# PROC099B_LC_Filtering_Reference.net
KiCad netlist of a schematic drawn in Altium Designer
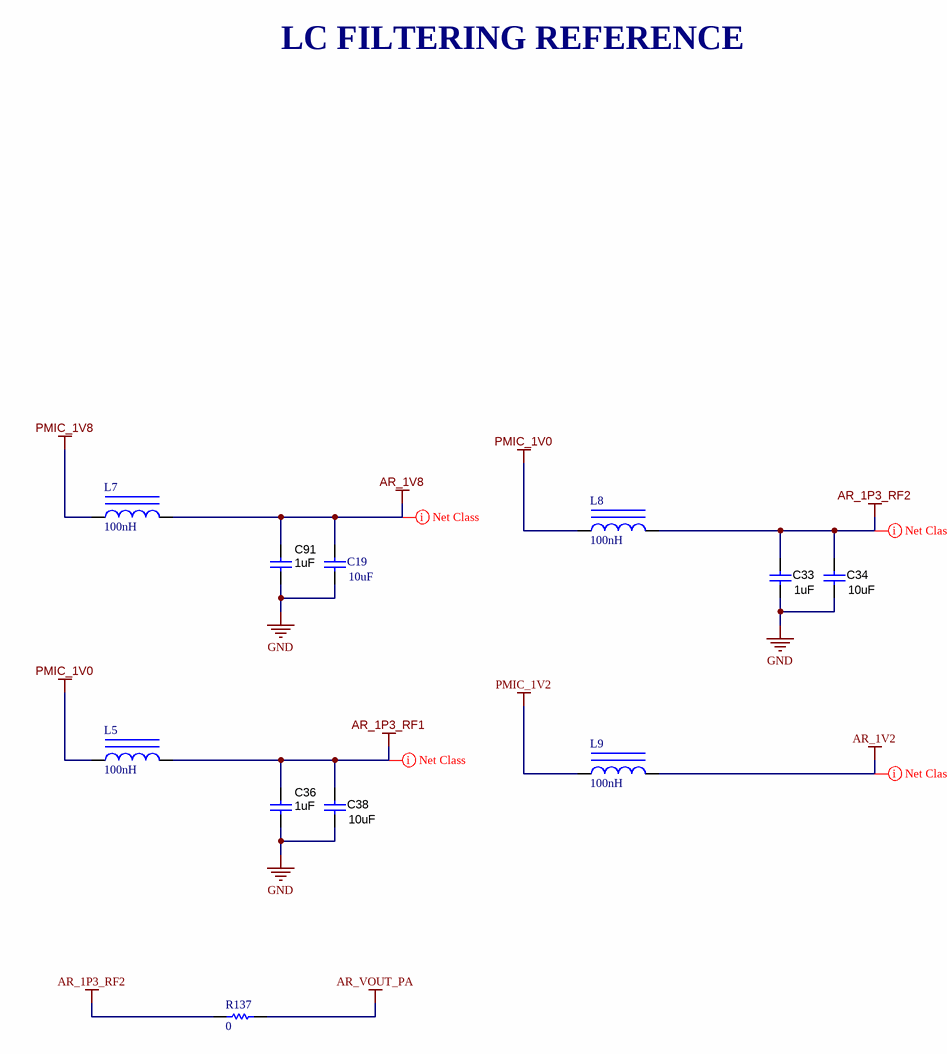
[diagram p0: PROC099B_LC_Filtering_Reference.SchDoc]

(export (version "E")
  (design (tool "Eeschema 10.0.6"))
  (components
    (comp (ref "C19")
      (value "GCM21BR71A106KE22L")
      (footprint "0805_HV")
      (description "CAP, CERM, 10 uF, 10 V, +/- 10%, X7R, 0805")
      (fields
        (field (name "MANUFACTURER") "MuRata")
        (field (name "VALUEDISPLAYED") "10uF")
        (field (name "PUBLISHER") "Texas Instruments")
      )
      (libsource (lib "Altium Vault - TI") (part "Capacitor"))
    )
    (comp (ref "C33")
      (value "GCM188R71C105KA64D")
      (footprint "0603")
      (description "CAP, CERM, 1 uF, 16 V, +/- 10%, X7R, AEC-Q200 Grade 1, 0603")
      (fields
        (field (name "MANUFACTURER") "MuRata")
        (field (name "VALUEDISPLAYED") "1uF")
        (field (name "PUBLISHER") "Texas Instruments")
      )
      (libsource (lib "Altium Vault - TI") (part "Capacitor"))
    )
    (comp (ref "C34")
      (value "GCM21BR71A106KE22L")
      (footprint "0805_HV")
      (description "CAP, CERM, 10 uF, 10 V, +/- 10%, X7R, 0805")
      (fields
        (field (name "MANUFACTURER") "MuRata")
        (field (name "VALUEDISPLAYED") "10uF")
        (field (name "PUBLISHER") "Texas Instruments")
      )
      (libsource (lib "Altium Vault - TI") (part "CMP-0008017-2"))
    )
    (comp (ref "C36")
      (value "GCM188R71C105KA64D")
      (footprint "0603")
      (description "CAP, CERM, 1 uF, 16 V, +/- 10%, X7R, AEC-Q200 Grade 1, 0603")
      (fields
        (field (name "MANUFACTURER") "MuRata")
        (field (name "VALUEDISPLAYED") "1uF")
        (field (name "PUBLISHER") "Texas Instruments")
      )
      (libsource (lib "Altium Vault - TI") (part "Capacitor"))
    )
    (comp (ref "C38")
      (value "GCM21BR71A106KE22L")
      (footprint "0805_HV")
      (description "CAP, CERM, 10 uF, 10 V, +/- 10%, X7R, 0805")
      (fields
        (field (name "MANUFACTURER") "MuRata")
        (field (name "VALUEDISPLAYED") "10uF")
        (field (name "PUBLISHER") "Texas Instruments")
      )
      (libsource (lib "Altium Vault - TI") (part "CMP-0008017-2"))
    )
    (comp (ref "C91")
      (value "GCM188R71C105KA64D")
      (footprint "0603")
      (description "CAP, CERM, 1 uF, 16 V, +/- 10%, X7R, AEC-Q200 Grade 1, 0603")
      (fields
        (field (name "MANUFACTURER") "MuRata")
        (field (name "VALUEDISPLAYED") "1uF")
        (field (name "PUBLISHER") "Texas Instruments")
      )
      (libsource (lib "Altium Vault - TI") (part "Capacitor"))
    )
    (comp (ref "L5")
      (value "NLCV32T-R10M-EFRD")
      (footprint "NLCV32")
      (description "Inductor, Wirewound, Ferrite, 100 nH, 2.85 A, 0.024 ohm, AEC-Q200 Grade 1, SMD")
      (fields (field (name "MANUFACTURER") "TDK") (field (name "VALUEDISPLAYED") "100nH"))
      (libsource (lib "Altium Vault - TI") (part "Inductor_Iron"))
    )
    (comp (ref "L7")
      (value "NLCV32T-R10M-EFRD")
      (footprint "NLCV32")
      (description "Inductor, Wirewound, Ferrite, 100 nH, 2.85 A, 0.024 ohm, AEC-Q200 Grade 1, SMD")
      (fields (field (name "MANUFACTURER") "TDK") (field (name "VALUEDISPLAYED") "100nH"))
      (libsource (lib "Altium Vault - TI") (part "Inductor_Iron"))
    )
    (comp (ref "L8")
      (value "NLCV32T-R10M-EFRD")
      (footprint "NLCV32")
      (description "Inductor, Wirewound, Ferrite, 100 nH, 2.85 A, 0.024 ohm, AEC-Q200 Grade 1, SMD")
      (fields (field (name "MANUFACTURER") "TDK") (field (name "VALUEDISPLAYED") "100nH"))
      (libsource (lib "Altium Vault - TI") (part "Inductor_Iron"))
    )
    (comp (ref "L9")
      (value "NLCV32T-R10M-EFRD")
      (footprint "NLCV32")
      (description "Inductor, Wirewound, Ferrite, 100 nH, 2.85 A, 0.024 ohm, AEC-Q200 Grade 1, SMD")
      (fields (field (name "MANUFACTURER") "TDK") (field (name "VALUEDISPLAYED") "100nH"))
      (libsource (lib "Altium Vault - TI") (part "Inductor_Iron"))
    )
    (comp (ref "R137")
      (value "MCT06030Z0000ZP500")
      (footprint "0603")
      (description "RES, 0, 5%, 0.125 W, 0603")
      (fields
        (field (name "MANUFACTURER") "Vishay/Beyschlag")
        (field (name "VALUEDISPLAYED") "0")
        (field (name "PUBLISHER") "Texas Instruments")
      )
      (libsource (lib "Altium Vault - TI") (part "CMP-0025884-3"))
    )
  )
  (nets
    (net (code "1") (name "AR_1P3_RF1") (class "Default")
      (node (ref "C36") (pin "2") (pinfunction "2_2") (pintype "passive"))
      (node (ref "C38") (pin "2") (pinfunction "2_2") (pintype "passive"))
      (node (ref "L5") (pin "2") (pinfunction "2_2") (pintype "passive"))
    )
    (net (code "2") (name "AR_1P3_RF2") (class "Default")
      (node (ref "C33") (pin "2") (pinfunction "2_2") (pintype "passive"))
      (node (ref "C34") (pin "2") (pinfunction "2_2") (pintype "passive"))
      (node (ref "L8") (pin "2") (pinfunction "2_2") (pintype "passive"))
      (node (ref "R137") (pin "1") (pinfunction "1_1") (pintype "passive"))
    )
    (net (code "3") (name "AR_1V2") (class "Default")
      (node (ref "L9") (pin "2") (pinfunction "2_2") (pintype "passive"))
    )
    (net (code "4") (name "AR_1V8") (class "Default")
      (node (ref "C19") (pin "1") (pinfunction "1_1") (pintype "passive"))
      (node (ref "C91") (pin "2") (pinfunction "2_2") (pintype "passive"))
      (node (ref "L7") (pin "2") (pinfunction "2_2") (pintype "passive"))
    )
    (net (code "5") (name "AR_VOUT_PA") (class "Default")
      (node (ref "R137") (pin "2") (pinfunction "2_2") (pintype "passive"))
    )
    (net (code "6") (name "GND") (class "Default")
      (node (ref "C19") (pin "2") (pinfunction "2_2") (pintype "passive"))
      (node (ref "C33") (pin "1") (pinfunction "1_1") (pintype "passive"))
      (node (ref "C34") (pin "1") (pinfunction "1_1") (pintype "passive"))
      (node (ref "C36") (pin "1") (pinfunction "1_1") (pintype "passive"))
      (node (ref "C38") (pin "1") (pinfunction "1_1") (pintype "passive"))
      (node (ref "C91") (pin "1") (pinfunction "1_1") (pintype "passive"))
    )
    (net (code "7") (name "PMIC_1V0") (class "Default")
      (node (ref "L5") (pin "1") (pinfunction "1_1") (pintype "passive"))
      (node (ref "L8") (pin "1") (pinfunction "1_1") (pintype "passive"))
    )
    (net (code "8") (name "PMIC_1V2") (class "Default")
      (node (ref "L9") (pin "1") (pinfunction "1_1") (pintype "passive"))
    )
    (net (code "9") (name "PMIC_1V8") (class "Default")
      (node (ref "L7") (pin "1") (pinfunction "1_1") (pintype "passive"))
    )
  )
)
